# USB3300-EZK-PHY.net
KiCad netlist of a schematic drawn in Altium Designer
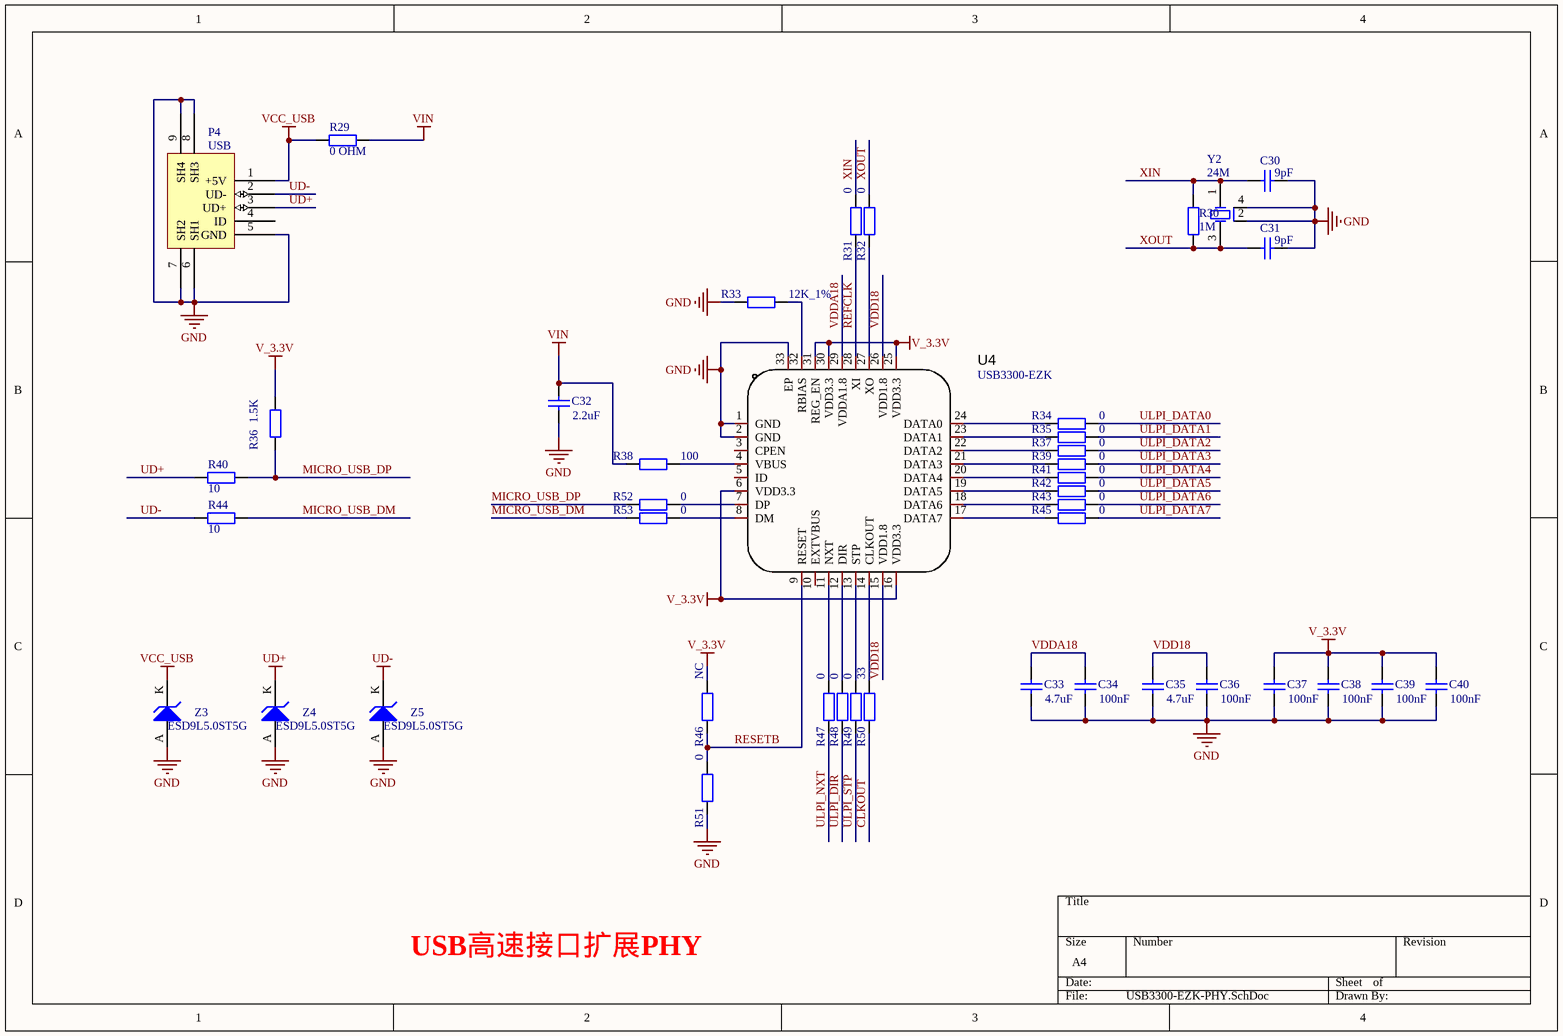
[diagram p0: USB3300-EZK-PHY.SchDoc]

(export (version "E")
  (design (tool "Eeschema 10.0.6"))
  (components
    (comp (ref "C30")
      (value "9pF")
      (footprint "C0402")
      (description "Capacitor")
      (fields (field (name "PUBLISHER") "Altium Limited"))
      (libsource (lib "Miscellaneous Devices") (part "Cap"))
    )
    (comp (ref "C31")
      (value "9pF")
      (footprint "C0402")
      (description "Capacitor")
      (fields (field (name "PUBLISHER") "Altium Limited"))
      (libsource (lib "Miscellaneous Devices") (part "Cap"))
    )
    (comp (ref "C32")
      (value "2.2uF")
      (footprint "C0402")
      (description "Capacitor")
      (fields (field (name "PUBLISHER") "Altium Limited"))
      (libsource (lib "Miscellaneous Devices") (part "Cap"))
    )
    (comp (ref "C33")
      (value "4.7uF")
      (footprint "C0402")
      (description "Capacitor")
      (fields (field (name "PUBLISHER") "Altium Limited"))
      (libsource (lib "Miscellaneous Devices") (part "Cap"))
    )
    (comp (ref "C34")
      (value "100nF")
      (footprint "C0402")
      (description "Capacitor")
      (fields (field (name "PUBLISHER") "Altium Limited"))
      (libsource (lib "Miscellaneous Devices") (part "Cap"))
    )
    (comp (ref "C35")
      (value "4.7uF")
      (footprint "C0402")
      (description "Capacitor")
      (fields (field (name "PUBLISHER") "Altium Limited"))
      (libsource (lib "Miscellaneous Devices") (part "Cap"))
    )
    (comp (ref "C36")
      (value "100nF")
      (footprint "C0402")
      (description "Capacitor")
      (fields (field (name "PUBLISHER") "Altium Limited"))
      (libsource (lib "Miscellaneous Devices") (part "Cap"))
    )
    (comp (ref "C37")
      (value "100nF")
      (footprint "C0402")
      (description "Capacitor")
      (fields (field (name "PUBLISHER") "Altium Limited"))
      (libsource (lib "Miscellaneous Devices") (part "Cap"))
    )
    (comp (ref "C38")
      (value "100nF")
      (footprint "C0402")
      (description "Capacitor")
      (fields (field (name "PUBLISHER") "Altium Limited"))
      (libsource (lib "Miscellaneous Devices") (part "Cap"))
    )
    (comp (ref "C39")
      (value "100nF")
      (footprint "C0402")
      (description "Capacitor")
      (fields (field (name "PUBLISHER") "Altium Limited"))
      (libsource (lib "Miscellaneous Devices") (part "Cap"))
    )
    (comp (ref "C40")
      (value "100nF")
      (footprint "C0402")
      (description "Capacitor")
      (fields (field (name "PUBLISHER") "Altium Limited"))
      (libsource (lib "Miscellaneous Devices") (part "Cap"))
    )
    (comp (ref "P4") (value "USB") (footprint "USB 牛角头") (libsource (lib "XBR820_1") (part "USB")))
    (comp (ref "R29")
      (value "0 OHM")
      (footprint "R0402")
      (description "Resistor")
      (fields (field (name "PUBLISHER") "Altium Limited"))
      (libsource (lib "XBR820_1") (part "Res2"))
    )
    (comp (ref "R30")
      (value "1M")
      (footprint "R0402")
      (description "Resistor")
      (fields (field (name "PUBLISHER") "Altium Limited"))
      (libsource (lib "") (part "Res2_3"))
    )
    (comp (ref "R31")
      (value "0")
      (footprint "R0402")
      (description "Resistor")
      (fields (field (name "PUBLISHER") "Altium Limited"))
      (libsource (lib "") (part "Res2_1"))
    )
    (comp (ref "R32")
      (value "0")
      (footprint "R0402")
      (description "Resistor")
      (fields (field (name "PUBLISHER") "Altium Limited"))
      (libsource (lib "") (part "Res2_1"))
    )
    (comp (ref "R33")
      (value "12K_1%")
      (footprint "R0402")
      (description "Resistor")
      (fields (field (name "PUBLISHER") "Altium Limited"))
      (libsource (lib "Miscellaneous Devices") (part "Res2"))
    )
    (comp (ref "R34")
      (value "0")
      (footprint "R0402")
      (description "Resistor")
      (fields (field (name "PUBLISHER") "Altium Limited"))
      (libsource (lib "Miscellaneous Devices") (part "Res2"))
    )
    (comp (ref "R35")
      (value "0")
      (footprint "R0402")
      (description "Resistor")
      (fields (field (name "PUBLISHER") "Altium Limited"))
      (libsource (lib "Miscellaneous Devices") (part "Res2"))
    )
    (comp (ref "R36")
      (value "1.5K")
      (footprint "R0402")
      (description "Resistor")
      (fields (field (name "PUBLISHER") "Altium Limited"))
      (libsource (lib "") (part "Res2_1"))
    )
    (comp (ref "R37")
      (value "0")
      (footprint "R0402")
      (description "Resistor")
      (fields (field (name "PUBLISHER") "Altium Limited"))
      (libsource (lib "Miscellaneous Devices") (part "Res2"))
    )
    (comp (ref "R38")
      (value "100")
      (footprint "R0402")
      (description "Resistor")
      (fields (field (name "PUBLISHER") "Altium Limited"))
      (libsource (lib "Miscellaneous Devices") (part "Res2"))
    )
    (comp (ref "R39")
      (value "0")
      (footprint "R0402")
      (description "Resistor")
      (fields (field (name "PUBLISHER") "Altium Limited"))
      (libsource (lib "Miscellaneous Devices") (part "Res2"))
    )
    (comp (ref "R40")
      (value "10")
      (footprint "R0402")
      (description "Resistor")
      (fields (field (name "PUBLISHER") "Altium Limited"))
      (libsource (lib "") (part "Res2_2"))
    )
    (comp (ref "R41")
      (value "0")
      (footprint "R0402")
      (description "Resistor")
      (fields (field (name "PUBLISHER") "Altium Limited"))
      (libsource (lib "Miscellaneous Devices") (part "Res2"))
    )
    (comp (ref "R42")
      (value "0")
      (footprint "R0402")
      (description "Resistor")
      (fields (field (name "PUBLISHER") "Altium Limited"))
      (libsource (lib "Miscellaneous Devices") (part "Res2"))
    )
    (comp (ref "R43")
      (value "0")
      (footprint "R0402")
      (description "Resistor")
      (fields (field (name "PUBLISHER") "Altium Limited"))
      (libsource (lib "Miscellaneous Devices") (part "Res2"))
    )
    (comp (ref "R44")
      (value "10")
      (footprint "R0402")
      (description "Resistor")
      (fields (field (name "PUBLISHER") "Altium Limited"))
      (libsource (lib "") (part "Res2_2"))
    )
    (comp (ref "R45")
      (value "0")
      (footprint "R0402")
      (description "Resistor")
      (fields (field (name "PUBLISHER") "Altium Limited"))
      (libsource (lib "Miscellaneous Devices") (part "Res2"))
    )
    (comp (ref "R46")
      (value "NC")
      (footprint "R0402")
      (description "Resistor")
      (fields (field (name "PUBLISHER") "Altium Limited"))
      (libsource (lib "") (part "Res2_1"))
    )
    (comp (ref "R47")
      (value "0")
      (footprint "R0402")
      (description "Resistor")
      (fields (field (name "PUBLISHER") "Altium Limited"))
      (libsource (lib "") (part "Res2_1"))
    )
    (comp (ref "R48")
      (value "0")
      (footprint "R0402")
      (description "Resistor")
      (fields (field (name "PUBLISHER") "Altium Limited"))
      (libsource (lib "") (part "Res2_1"))
    )
    (comp (ref "R49")
      (value "0")
      (footprint "R0402")
      (description "Resistor")
      (fields (field (name "PUBLISHER") "Altium Limited"))
      (libsource (lib "") (part "Res2_1"))
    )
    (comp (ref "R50")
      (value "33")
      (footprint "R0402")
      (description "Resistor")
      (fields (field (name "PUBLISHER") "Altium Limited"))
      (libsource (lib "") (part "Res2_1"))
    )
    (comp (ref "R51")
      (value "0")
      (footprint "R0402")
      (description "Resistor")
      (fields (field (name "PUBLISHER") "Altium Limited"))
      (libsource (lib "") (part "Res2_1"))
    )
    (comp (ref "R52")
      (value "0")
      (footprint "R0402")
      (description "Resistor")
      (fields (field (name "PUBLISHER") "Altium Limited"))
      (libsource (lib "") (part "Res2_2"))
    )
    (comp (ref "R53")
      (value "0")
      (footprint "R0402")
      (description "Resistor")
      (fields (field (name "PUBLISHER") "Altium Limited"))
      (libsource (lib "") (part "Res2_2"))
    )
    (comp (ref "U4")
      (value "USB3300-EZK")
      (footprint "QFN-32_L5.0-W5.0-P0.50-BL-EP3.4")
      (fields (field (name "MANUFACTURER") "MICROCHIP(美国微芯)"))
      (libsource (lib "altium-import") (part "root_0_USB3300-EZK_"))
    )
    (comp (ref "Y2")
      (value "24M")
      (footprint "CRYSTAL_3.2*2.5")
      (libsource (lib "schlib-yves20140829") (part "CRYSTAL-PASSIVE_3225"))
    )
    (comp (ref "Z3")
      (value "ESD9L5.0ST5G")
      (footprint "SOD-923")
      (description "Zener Diode")
      (fields (field (name "PUBLISHER") "Altium Limited"))
      (libsource (lib "Miscellaneous Devices") (part "D Zener"))
    )
    (comp (ref "Z4")
      (value "ESD9L5.0ST5G")
      (footprint "SOD-923")
      (description "Zener Diode")
      (fields (field (name "PUBLISHER") "Altium Limited"))
      (libsource (lib "Miscellaneous Devices") (part "D Zener"))
    )
    (comp (ref "Z5")
      (value "ESD9L5.0ST5G")
      (footprint "SOD-923")
      (description "Zener Diode")
      (fields (field (name "PUBLISHER") "Altium Limited"))
      (libsource (lib "Miscellaneous Devices") (part "D Zener"))
    )
  )
  (nets
    (net (code "1") (name "/CLKOUT") (class "Default")
      (node (ref "R50") (pin "2") (pinfunction "2_2") (pintype "passive"))
    )
    (net (code "2") (name "/MICRO_USB_DM") (class "Default")
      (node (ref "R44") (pin "2") (pinfunction "2_2") (pintype "passive"))
      (node (ref "R53") (pin "1") (pinfunction "1_1") (pintype "passive"))
    )
    (net (code "3") (name "/MICRO_USB_DP") (class "Default")
      (node (ref "R36") (pin "2") (pinfunction "2_2") (pintype "passive"))
      (node (ref "R40") (pin "2") (pinfunction "2_2") (pintype "passive"))
      (node (ref "R52") (pin "1") (pinfunction "1_1") (pintype "passive"))
    )
    (net (code "4") (name "/REFCLK") (class "Default")
      (node (ref "R31") (pin "2") (pinfunction "2_2") (pintype "passive"))
      (node (ref "U4") (pin "28") (pinfunction "XI_28") (pintype "passive"))
    )
    (net (code "5") (name "/RESETB") (class "Default")
      (node (ref "R46") (pin "2") (pinfunction "2_2") (pintype "passive"))
      (node (ref "R51") (pin "1") (pinfunction "1_1") (pintype "passive"))
      (node (ref "U4") (pin "9") (pinfunction "RESET_9") (pintype "passive"))
    )
    (net (code "6") (name "/ULPI_DATA0") (class "Default")
      (node (ref "R34") (pin "1") (pinfunction "1_1") (pintype "passive"))
    )
    (net (code "7") (name "/ULPI_DATA1") (class "Default")
      (node (ref "R35") (pin "1") (pinfunction "1_1") (pintype "passive"))
    )
    (net (code "8") (name "/ULPI_DATA2") (class "Default")
      (node (ref "R37") (pin "1") (pinfunction "1_1") (pintype "passive"))
    )
    (net (code "9") (name "/ULPI_DATA3") (class "Default")
      (node (ref "R39") (pin "1") (pinfunction "1_1") (pintype "passive"))
    )
    (net (code "10") (name "/ULPI_DATA4") (class "Default")
      (node (ref "R41") (pin "1") (pinfunction "1_1") (pintype "passive"))
    )
    (net (code "11") (name "/ULPI_DATA5") (class "Default")
      (node (ref "R42") (pin "1") (pinfunction "1_1") (pintype "passive"))
    )
    (net (code "12") (name "/ULPI_DATA6") (class "Default")
      (node (ref "R43") (pin "1") (pinfunction "1_1") (pintype "passive"))
    )
    (net (code "13") (name "/ULPI_DATA7") (class "Default")
      (node (ref "R45") (pin "1") (pinfunction "1_1") (pintype "passive"))
    )
    (net (code "14") (name "/ULPI_DIR") (class "Default")
      (node (ref "R48") (pin "2") (pinfunction "2_2") (pintype "passive"))
    )
    (net (code "15") (name "/ULPI_NXT") (class "Default")
      (node (ref "R47") (pin "2") (pinfunction "2_2") (pintype "passive"))
    )
    (net (code "16") (name "/ULPI_STP") (class "Default")
      (node (ref "R49") (pin "2") (pinfunction "2_2") (pintype "passive"))
    )
    (net (code "17") (name "/VDD18") (class "Default")
      (node (ref "C35") (pin "1") (pinfunction "1_1") (pintype "passive"))
      (node (ref "C36") (pin "1") (pinfunction "1_1") (pintype "passive"))
      (node (ref "U4") (pin "15") (pinfunction "VDD1.8_15") (pintype "passive"))
      (node (ref "U4") (pin "26") (pinfunction "VDD1.8_26") (pintype "passive"))
    )
    (net (code "18") (name "/VDDA18") (class "Default")
      (node (ref "C33") (pin "1") (pinfunction "1_1") (pintype "passive"))
      (node (ref "C34") (pin "1") (pinfunction "1_1") (pintype "passive"))
      (node (ref "U4") (pin "29") (pinfunction "VDDA1.8_29") (pintype "passive"))
    )
    (net (code "19") (name "/XIN") (class "Default")
      (node (ref "C30") (pin "1") (pinfunction "1_1") (pintype "passive"))
      (node (ref "R30") (pin "2") (pinfunction "2_2") (pintype "passive"))
      (node (ref "R31") (pin "1") (pinfunction "1_1") (pintype "passive"))
      (node (ref "Y2") (pin "1") (pinfunction "INPUT_1") (pintype "passive"))
    )
    (net (code "20") (name "/XOUT") (class "Default")
      (node (ref "C31") (pin "1") (pinfunction "1_1") (pintype "passive"))
      (node (ref "R30") (pin "1") (pinfunction "1_1") (pintype "passive"))
      (node (ref "R32") (pin "1") (pinfunction "1_1") (pintype "passive"))
      (node (ref "Y2") (pin "3") (pinfunction "OUTPUT_3") (pintype "passive"))
    )
    (net (code "21") (name "GND") (class "Default")
      (node (ref "C30") (pin "2") (pinfunction "2_2") (pintype "passive"))
      (node (ref "C31") (pin "2") (pinfunction "2_2") (pintype "passive"))
      (node (ref "C32") (pin "2") (pinfunction "2_2") (pintype "passive"))
      (node (ref "C33") (pin "2") (pinfunction "2_2") (pintype "passive"))
      (node (ref "C34") (pin "2") (pinfunction "2_2") (pintype "passive"))
      (node (ref "C35") (pin "2") (pinfunction "2_2") (pintype "passive"))
      (node (ref "C36") (pin "2") (pinfunction "2_2") (pintype "passive"))
      (node (ref "C37") (pin "2") (pinfunction "2_2") (pintype "passive"))
      (node (ref "C38") (pin "2") (pinfunction "2_2") (pintype "passive"))
      (node (ref "C39") (pin "2") (pinfunction "2_2") (pintype "passive"))
      (node (ref "C40") (pin "2") (pinfunction "2_2") (pintype "passive"))
      (node (ref "P4") (pin "5") (pinfunction "GND_5") (pintype "power_in"))
      (node (ref "P4") (pin "6") (pinfunction "SH1_6") (pintype "power_in"))
      (node (ref "P4") (pin "7") (pinfunction "SH2_7") (pintype "passive"))
      (node (ref "P4") (pin "8") (pinfunction "SH3_8") (pintype "power_in"))
      (node (ref "P4") (pin "9") (pinfunction "SH4_9") (pintype "passive"))
      (node (ref "R33") (pin "2") (pinfunction "2_2") (pintype "passive"))
      (node (ref "R51") (pin "2") (pinfunction "2_2") (pintype "passive"))
      (node (ref "U4") (pin "1") (pinfunction "GND_1") (pintype "passive"))
      (node (ref "U4") (pin "2") (pinfunction "GND_2") (pintype "passive"))
      (node (ref "U4") (pin "33") (pinfunction "EP_33") (pintype "passive"))
      (node (ref "Y2") (pin "2") (pinfunction "GROUND_2") (pintype "passive"))
      (node (ref "Y2") (pin "4") (pinfunction "GROUND_4") (pintype "passive"))
      (node (ref "Z3") (pin "A") (pinfunction "A_A") (pintype "passive"))
      (node (ref "Z4") (pin "A") (pinfunction "A_A") (pintype "passive"))
      (node (ref "Z5") (pin "A") (pinfunction "A_A") (pintype "passive"))
    )
    (net (code "22") (name "Net-(U4-CLKOUT)") (class "Default")
      (node (ref "R50") (pin "1") (pinfunction "1_1") (pintype "passive"))
      (node (ref "U4") (pin "14") (pinfunction "CLKOUT_14") (pintype "passive"))
    )
    (net (code "23") (name "Net-(U4-DATA0)") (class "Default")
      (node (ref "R34") (pin "2") (pinfunction "2_2") (pintype "passive"))
      (node (ref "U4") (pin "24") (pinfunction "DATA0_24") (pintype "passive"))
    )
    (net (code "24") (name "Net-(U4-DATA1)") (class "Default")
      (node (ref "R35") (pin "2") (pinfunction "2_2") (pintype "passive"))
      (node (ref "U4") (pin "23") (pinfunction "DATA1_23") (pintype "passive"))
    )
    (net (code "25") (name "Net-(U4-DATA2)") (class "Default")
      (node (ref "R37") (pin "2") (pinfunction "2_2") (pintype "passive"))
      (node (ref "U4") (pin "22") (pinfunction "DATA2_22") (pintype "passive"))
    )
    (net (code "26") (name "Net-(U4-DATA3)") (class "Default")
      (node (ref "R39") (pin "2") (pinfunction "2_2") (pintype "passive"))
      (node (ref "U4") (pin "21") (pinfunction "DATA3_21") (pintype "passive"))
    )
    (net (code "27") (name "Net-(U4-DATA4)") (class "Default")
      (node (ref "R41") (pin "2") (pinfunction "2_2") (pintype "passive"))
      (node (ref "U4") (pin "20") (pinfunction "DATA4_20") (pintype "passive"))
    )
    (net (code "28") (name "Net-(U4-DATA5)") (class "Default")
      (node (ref "R42") (pin "2") (pinfunction "2_2") (pintype "passive"))
      (node (ref "U4") (pin "19") (pinfunction "DATA5_19") (pintype "passive"))
    )
    (net (code "29") (name "Net-(U4-DATA6)") (class "Default")
      (node (ref "R43") (pin "2") (pinfunction "2_2") (pintype "passive"))
      (node (ref "U4") (pin "18") (pinfunction "DATA6_18") (pintype "passive"))
    )
    (net (code "30") (name "Net-(U4-DATA7)") (class "Default")
      (node (ref "R45") (pin "2") (pinfunction "2_2") (pintype "passive"))
      (node (ref "U4") (pin "17") (pinfunction "DATA7_17") (pintype "passive"))
    )
    (net (code "31") (name "Net-(U4-DIR)") (class "Default")
      (node (ref "R48") (pin "1") (pinfunction "1_1") (pintype "passive"))
      (node (ref "U4") (pin "12") (pinfunction "DIR_12") (pintype "passive"))
    )
    (net (code "32") (name "Net-(U4-DM)") (class "Default")
      (node (ref "R53") (pin "2") (pinfunction "2_2") (pintype "passive"))
      (node (ref "U4") (pin "8") (pinfunction "DM_8") (pintype "passive"))
    )
    (net (code "33") (name "Net-(U4-DP)") (class "Default")
      (node (ref "R52") (pin "2") (pinfunction "2_2") (pintype "passive"))
      (node (ref "U4") (pin "7") (pinfunction "DP_7") (pintype "passive"))
    )
    (net (code "34") (name "Net-(U4-NXT)") (class "Default")
      (node (ref "R47") (pin "1") (pinfunction "1_1") (pintype "passive"))
      (node (ref "U4") (pin "11") (pinfunction "NXT_11") (pintype "passive"))
    )
    (net (code "35") (name "Net-(U4-RBIAS)") (class "Default")
      (node (ref "R33") (pin "1") (pinfunction "1_1") (pintype "passive"))
      (node (ref "U4") (pin "32") (pinfunction "RBIAS_32") (pintype "passive"))
    )
    (net (code "36") (name "Net-(U4-STP)") (class "Default")
      (node (ref "R49") (pin "1") (pinfunction "1_1") (pintype "passive"))
      (node (ref "U4") (pin "13") (pinfunction "STP_13") (pintype "passive"))
    )
    (net (code "37") (name "Net-(U4-VBUS)") (class "Default")
      (node (ref "R38") (pin "1") (pinfunction "1_1") (pintype "passive"))
      (node (ref "U4") (pin "4") (pinfunction "VBUS_4") (pintype "passive"))
    )
    (net (code "38") (name "Net-(U4-XO)") (class "Default")
      (node (ref "R32") (pin "2") (pinfunction "2_2") (pintype "passive"))
      (node (ref "U4") (pin "27") (pinfunction "XO_27") (pintype "passive"))
    )
    (net (code "39") (name "UD+") (class "Default")
      (node (ref "P4") (pin "3") (pinfunction "UD+_3") (pintype "bidirectional"))
      (node (ref "R40") (pin "1") (pinfunction "1_1") (pintype "passive"))
      (node (ref "Z4") (pin "K") (pinfunction "K_K") (pintype "passive"))
    )
    (net (code "40") (name "UD-") (class "Default")
      (node (ref "P4") (pin "2") (pinfunction "UD-_2") (pintype "bidirectional"))
      (node (ref "R44") (pin "1") (pinfunction "1_1") (pintype "passive"))
      (node (ref "Z5") (pin "K") (pinfunction "K_K") (pintype "passive"))
    )
    (net (code "41") (name "VCC_USB") (class "Default")
      (node (ref "P4") (pin "1") (pinfunction "+5V_1") (pintype "power_in"))
      (node (ref "R29") (pin "2") (pinfunction "2_2") (pintype "passive"))
      (node (ref "Z3") (pin "K") (pinfunction "K_K") (pintype "passive"))
    )
    (net (code "42") (name "VIN") (class "Default")
      (node (ref "C32") (pin "1") (pinfunction "1_1") (pintype "passive"))
      (node (ref "R29") (pin "1") (pinfunction "1_1") (pintype "passive"))
      (node (ref "R38") (pin "2") (pinfunction "2_2") (pintype "passive"))
    )
    (net (code "43") (name "V_3.3V") (class "Default")
      (node (ref "C37") (pin "1") (pinfunction "1_1") (pintype "passive"))
      (node (ref "C38") (pin "1") (pinfunction "1_1") (pintype "passive"))
      (node (ref "C39") (pin "1") (pinfunction "1_1") (pintype "passive"))
      (node (ref "C40") (pin "1") (pinfunction "1_1") (pintype "passive"))
      (node (ref "R36") (pin "1") (pinfunction "1_1") (pintype "passive"))
      (node (ref "R46") (pin "1") (pinfunction "1_1") (pintype "passive"))
      (node (ref "U4") (pin "16") (pinfunction "VDD3.3_16") (pintype "passive"))
      (node (ref "U4") (pin "25") (pinfunction "VDD3.3_25") (pintype "passive"))
      (node (ref "U4") (pin "30") (pinfunction "VDD3.3_30") (pintype "passive"))
      (node (ref "U4") (pin "31") (pinfunction "REG_EN_31") (pintype "passive"))
      (node (ref "U4") (pin "6") (pinfunction "VDD3.3_6") (pintype "passive"))
    )
    (net (code "44") (name "unconnected-(P4-ID-Pad4)") (class "Default")
      (node (ref "P4") (pin "4") (pinfunction "ID_4") (pintype "passive"))
    )
    (net (code "45") (name "unconnected-(U4-CPEN-Pad3)") (class "Default")
      (node (ref "U4") (pin "3") (pinfunction "CPEN_3") (pintype "passive"))
    )
    (net (code "46") (name "unconnected-(U4-EXTVBUS-Pad10)") (class "Default")
      (node (ref "U4") (pin "10") (pinfunction "EXTVBUS_10") (pintype "passive"))
    )
    (net (code "47") (name "unconnected-(U4-ID-Pad5)") (class "Default")
      (node (ref "U4") (pin "5") (pinfunction "ID_5") (pintype "passive"))
    )
  )
)
